# SFT_MotorController1_0v.net
KiCad netlist of a schematic drawn in EAGLE
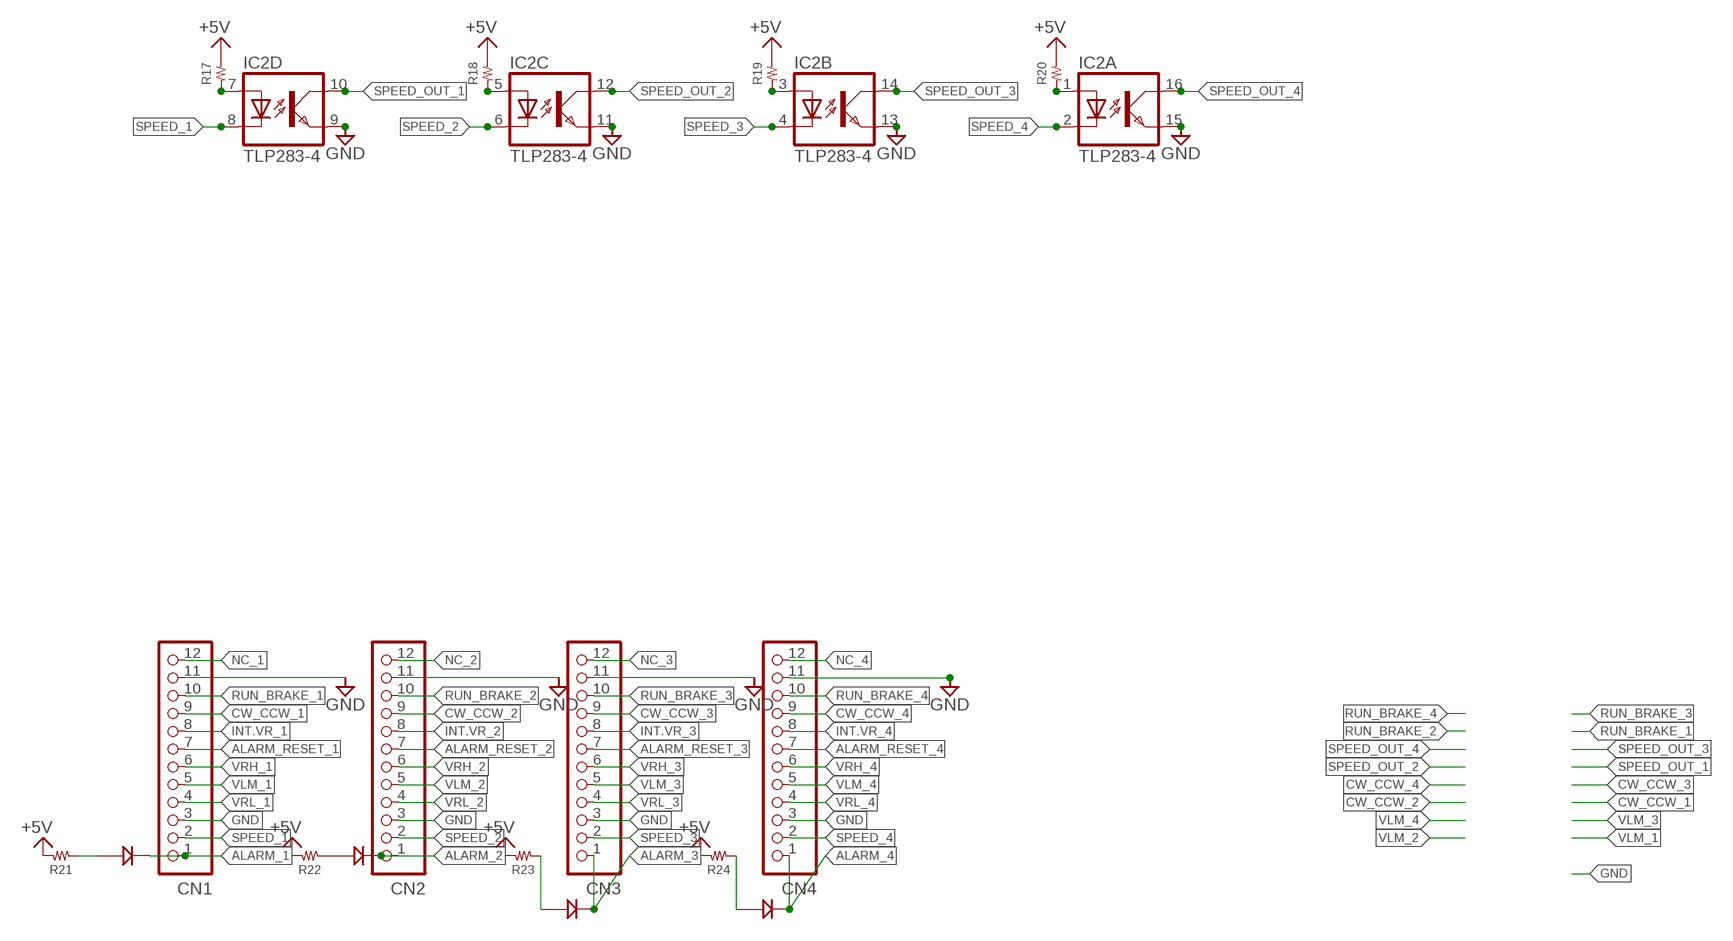
[diagram p0: schematic, sheet 1, part 1 of 2]
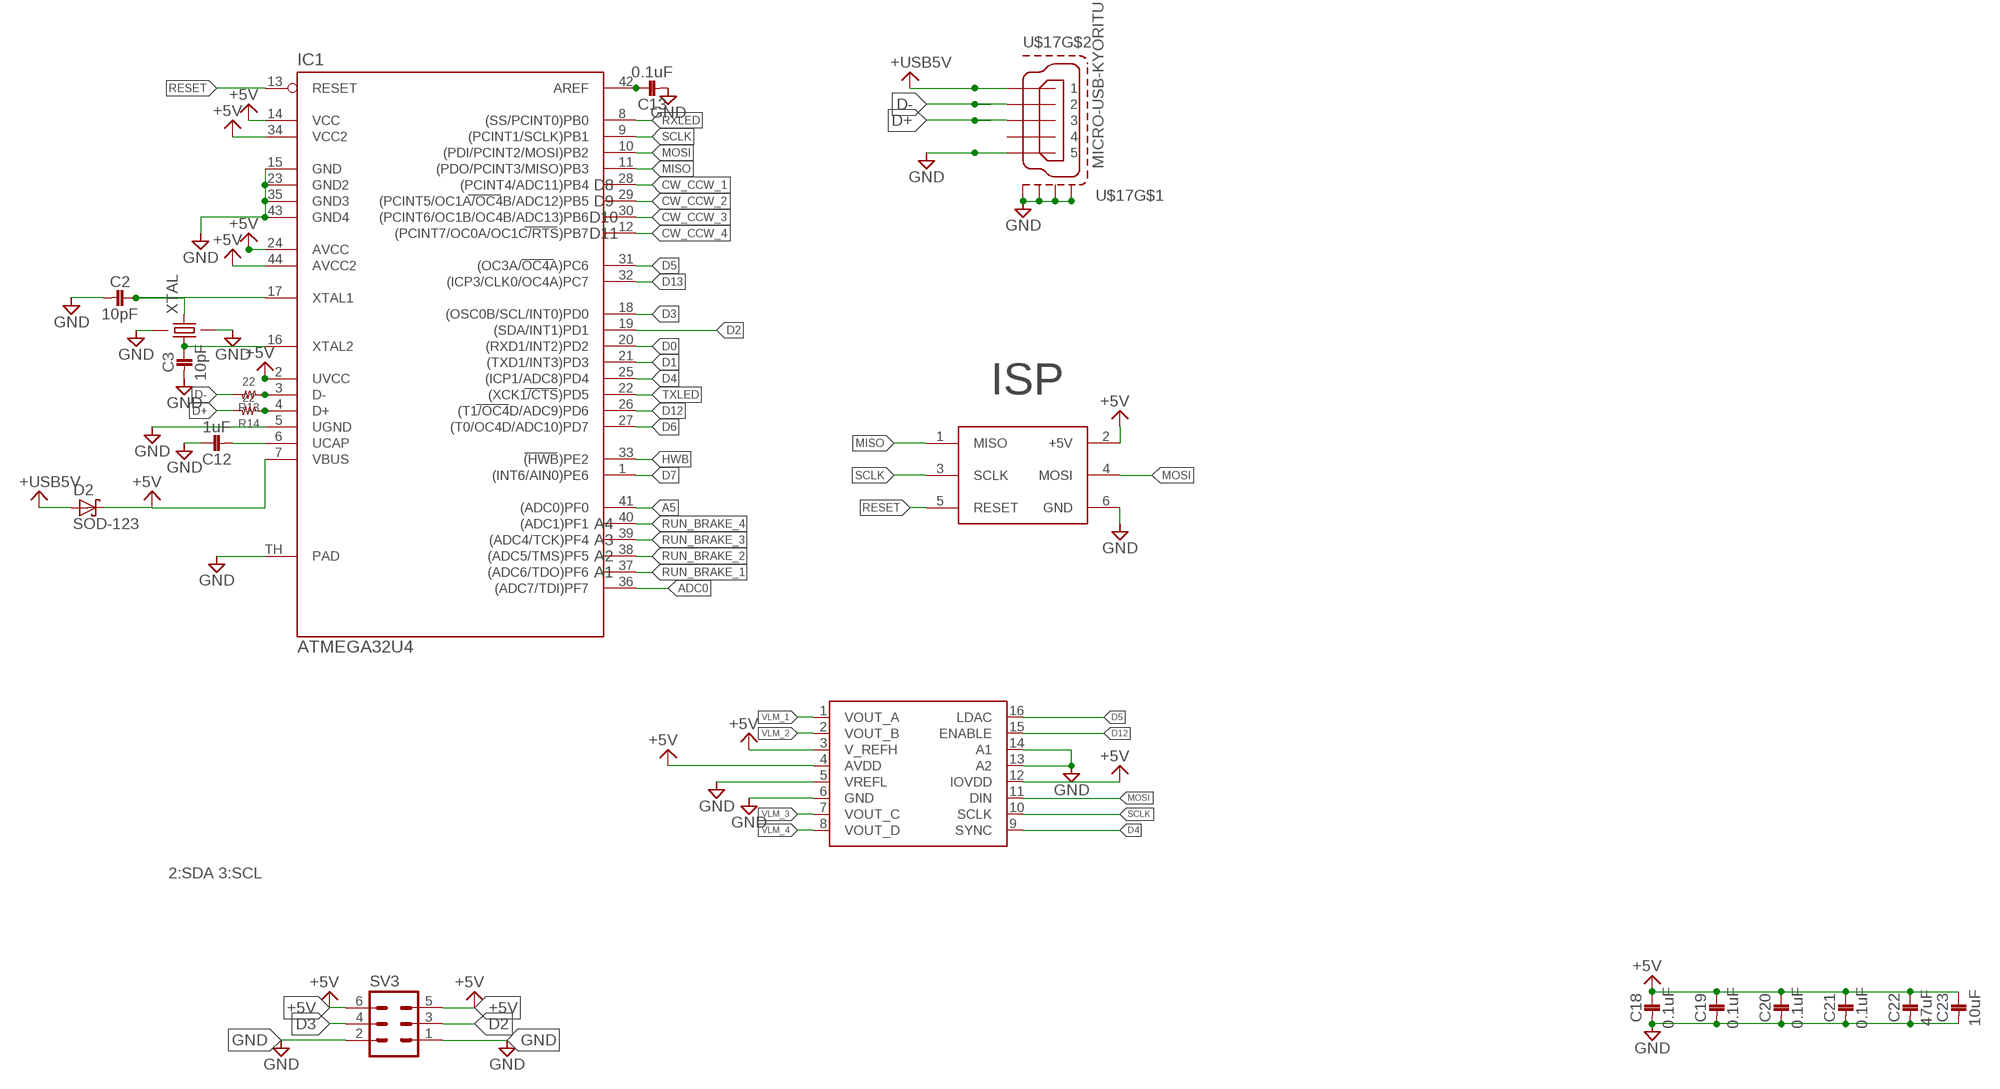
[diagram p1: schematic, sheet 1, part 2 of 2]

(export (version "E")
  (design (tool "Eeschema 10.0.6"))
  (components
    (comp (ref "C2")
      (value "10pF")
      (footprint "eagle-import:1005")
      (libsource (lib "eagle-import") (part "1005"))
    )
    (comp (ref "C3")
      (value "10pF")
      (footprint "eagle-import:1005")
      (libsource (lib "eagle-import") (part "1005"))
    )
    (comp (ref "C12")
      (value "1uF")
      (footprint "eagle-import:1005")
      (libsource (lib "eagle-import") (part "1005"))
    )
    (comp (ref "C13")
      (value "0.1uF")
      (footprint "eagle-import:1005")
      (libsource (lib "eagle-import") (part "1005"))
    )
    (comp (ref "C18")
      (value "0.1uF")
      (footprint "eagle-import:1005")
      (libsource (lib "eagle-import") (part "1005"))
    )
    (comp (ref "C19")
      (value "0.1uF")
      (footprint "eagle-import:1005")
      (libsource (lib "eagle-import") (part "1005"))
    )
    (comp (ref "C20")
      (value "0.1uF")
      (footprint "eagle-import:1005")
      (libsource (lib "eagle-import") (part "1005"))
    )
    (comp (ref "C21")
      (value "0.1uF")
      (footprint "eagle-import:1005")
      (libsource (lib "eagle-import") (part "1005"))
    )
    (comp (ref "C22")
      (value "47uF")
      (footprint "eagle-import:1608")
      (libsource (lib "eagle-import") (part "1608"))
    )
    (comp (ref "C23")
      (value "10uF")
      (footprint "eagle-import:1608")
      (libsource (lib "eagle-import") (part "1608"))
    )
    (comp (ref "CN1")
      (value "B12B-XASK-1")
      (footprint "eagle-import:B12B-XASK-1")
      (libsource (lib "eagle-import") (part "B12B-XASK-1"))
    )
    (comp (ref "CN2")
      (value "B12B-XASK-1")
      (footprint "eagle-import:B12B-XASK-1")
      (libsource (lib "eagle-import") (part "B12B-XASK-1"))
    )
    (comp (ref "CN3")
      (value "B12B-XASK-1")
      (footprint "eagle-import:B12B-XASK-1")
      (libsource (lib "eagle-import") (part "B12B-XASK-1"))
    )
    (comp (ref "CN4")
      (value "B12B-XASK-1")
      (footprint "eagle-import:B12B-XASK-1")
      (libsource (lib "eagle-import") (part "B12B-XASK-1"))
    )
    (comp (ref "D2")
      (value "SOD-123")
      (footprint "eagle-import:SOD_123")
      (libsource (lib "eagle-import") (part "SOD-123"))
    )
    (comp (ref "IC1")
      (value "ATMEGA32U4")
      (footprint "eagle-import:QFN-44-7X7")
      (libsource (lib "eagle-import") (part "ATMEGA32U4"))
    )
    (comp (ref "IC2")
      (value "TLP283-4")
      (footprint "eagle-import:MINI-FLAT-16")
      (libsource (lib "eagle-import") (part "TLP283-4"))
    )
    (comp (ref "IC3")
      (value "DAC7564")
      (footprint "eagle-import:TSSOP16")
      (libsource (lib "eagle-import") (part "DAC7564"))
    )
    (comp (ref "R13")
      (value "22")
      (footprint "eagle-import:1005")
      (libsource (lib "eagle-import") (part "RESISTOR_1005"))
    )
    (comp (ref "R14")
      (value "22")
      (footprint "eagle-import:1005")
      (libsource (lib "eagle-import") (part "RESISTOR_1005"))
    )
    (comp (ref "R17")
      (value "RESISTOR__SMD")
      (footprint "eagle-import:1608")
      (libsource (lib "eagle-import") (part "RESISTOR__SMD"))
    )
    (comp (ref "R18")
      (value "RESISTOR__SMD")
      (footprint "eagle-import:1608")
      (libsource (lib "eagle-import") (part "RESISTOR__SMD"))
    )
    (comp (ref "R19")
      (value "RESISTOR__SMD")
      (footprint "eagle-import:1608")
      (libsource (lib "eagle-import") (part "RESISTOR__SMD"))
    )
    (comp (ref "R20")
      (value "RESISTOR__SMD")
      (footprint "eagle-import:1608")
      (libsource (lib "eagle-import") (part "RESISTOR__SMD"))
    )
    (comp (ref "R21")
      (value "RESISTOR__SMD")
      (footprint "eagle-import:1608")
      (libsource (lib "eagle-import") (part "RESISTOR__SMD"))
    )
    (comp (ref "R22")
      (value "RESISTOR__SMD")
      (footprint "eagle-import:1608")
      (libsource (lib "eagle-import") (part "RESISTOR__SMD"))
    )
    (comp (ref "R23")
      (value "RESISTOR__SMD")
      (footprint "eagle-import:1608")
      (libsource (lib "eagle-import") (part "RESISTOR__SMD"))
    )
    (comp (ref "R24")
      (value "RESISTOR__SMD")
      (footprint "eagle-import:1608")
      (libsource (lib "eagle-import") (part "RESISTOR__SMD"))
    )
    (comp (ref "SV3")
      (value "ML6")
      (footprint "eagle-import:ML6")
      (libsource (lib "eagle-import") (part "ML6"))
    )
    (comp (ref "U$8")
      (value "ICSP")
      (footprint "eagle-import:ICSP")
      (libsource (lib "eagle-import") (part "ICSP"))
    )
    (comp (ref "U$17")
      (value "MICRO-USB-KYORITU")
      (footprint "eagle-import:ZX62R-B-5P")
      (libsource (lib "eagle-import") (part "MICRO-USB-KYORITU"))
    )
    (comp (ref "U$36")
      (value "3MMLED")
      (footprint "eagle-import:3MM")
      (libsource (lib "eagle-import") (part "3MMLED"))
    )
    (comp (ref "U$37")
      (value "3MMLED")
      (footprint "eagle-import:3MM")
      (libsource (lib "eagle-import") (part "3MMLED"))
    )
    (comp (ref "U$38")
      (value "3MMLED")
      (footprint "eagle-import:3MM")
      (libsource (lib "eagle-import") (part "3MMLED"))
    )
    (comp (ref "U$39")
      (value "3MMLED")
      (footprint "eagle-import:3MM")
      (libsource (lib "eagle-import") (part "3MMLED"))
    )
    (comp (ref "XTAL")
      (value "FA-238")
      (footprint "eagle-import:FA-238")
      (libsource (lib "eagle-import") (part "FA-238"))
    )
  )
  (nets
    (net (code "1") (name "+5V") (class "Default")
      (node (ref "C18") (pin "1") (pinfunction "1_1") (pintype "passive"))
      (node (ref "C19") (pin "1") (pinfunction "1_1") (pintype "passive"))
      (node (ref "C20") (pin "1") (pinfunction "1_1") (pintype "passive"))
      (node (ref "C21") (pin "1") (pinfunction "1_1") (pintype "passive"))
      (node (ref "C22") (pin "P$1") (pinfunction "1_P$1") (pintype "passive"))
      (node (ref "C23") (pin "P$1") (pinfunction "1_P$1") (pintype "passive"))
      (node (ref "D2") (pin "C") (pinfunction "C_C") (pintype "passive"))
      (node (ref "IC1") (pin "14") (pinfunction "VCC_14") (pintype "bidirectional"))
      (node (ref "IC1") (pin "2") (pinfunction "UVCC_2") (pintype "bidirectional"))
      (node (ref "IC1") (pin "24") (pinfunction "AVCC_24") (pintype "bidirectional"))
      (node (ref "IC1") (pin "34") (pinfunction "VCC2_34") (pintype "bidirectional"))
      (node (ref "IC1") (pin "44") (pinfunction "AVCC2_44") (pintype "bidirectional"))
      (node (ref "IC1") (pin "7") (pinfunction "VBUS_7") (pintype "bidirectional"))
      (node (ref "IC3") (pin "12") (pinfunction "IOVDD_12") (pintype "bidirectional"))
      (node (ref "IC3") (pin "3") (pinfunction "V_REFH_3") (pintype "bidirectional"))
      (node (ref "IC3") (pin "4") (pinfunction "AVDD_4") (pintype "bidirectional"))
      (node (ref "R17") (pin "2") (pinfunction "P$2_2") (pintype "passive"))
      (node (ref "R18") (pin "2") (pinfunction "P$2_2") (pintype "passive"))
      (node (ref "R19") (pin "2") (pinfunction "P$2_2") (pintype "passive"))
      (node (ref "R20") (pin "2") (pinfunction "P$2_2") (pintype "passive"))
      (node (ref "R21") (pin "2") (pinfunction "P$2_2") (pintype "passive"))
      (node (ref "R22") (pin "2") (pinfunction "P$2_2") (pintype "passive"))
      (node (ref "R23") (pin "2") (pinfunction "P$2_2") (pintype "passive"))
      (node (ref "R24") (pin "2") (pinfunction "P$2_2") (pintype "passive"))
      (node (ref "SV3") (pin "5") (pinfunction "5_5") (pintype "passive"))
      (node (ref "SV3") (pin "6") (pinfunction "6_6") (pintype "passive"))
      (node (ref "U$8") (pin "2") (pinfunction "+5V_2") (pintype "bidirectional"))
    )
    (net (code "2") (name "+USB5V") (class "Default")
      (node (ref "D2") (pin "A") (pinfunction "A_A") (pintype "passive"))
      (node (ref "U$17") (pin "5") (pinfunction "1_5") (pintype "input"))
    )
    (net (code "3") (name "A5") (class "Default")
      (node (ref "IC1") (pin "41") (pinfunction "(ADC0)PF0_41") (pintype "bidirectional"))
    )
    (net (code "4") (name "ADC0") (class "Default")
      (node (ref "IC1") (pin "36") (pinfunction "(ADC7/TDI)PF7_36") (pintype "bidirectional"))
    )
    (net (code "5") (name "ALARM_1") (class "Default")
      (node (ref "CN1") (pin "1") (pinfunction "1_1") (pintype "passive"))
      (node (ref "U$37") (pin "K") (pinfunction "K_K") (pintype "bidirectional"))
    )
    (net (code "6") (name "ALARM_2") (class "Default")
      (node (ref "CN2") (pin "1") (pinfunction "1_1") (pintype "passive"))
      (node (ref "U$38") (pin "K") (pinfunction "K_K") (pintype "bidirectional"))
    )
    (net (code "7") (name "ALARM_3") (class "Default")
      (node (ref "CN3") (pin "1") (pinfunction "1_1") (pintype "passive"))
      (node (ref "U$36") (pin "K") (pinfunction "K_K") (pintype "bidirectional"))
    )
    (net (code "8") (name "ALARM_4") (class "Default")
      (node (ref "CN4") (pin "1") (pinfunction "1_1") (pintype "passive"))
      (node (ref "U$39") (pin "K") (pinfunction "K_K") (pintype "bidirectional"))
    )
    (net (code "9") (name "ALARM_RESET_1") (class "Default")
      (node (ref "CN1") (pin "7") (pinfunction "7_7") (pintype "passive"))
    )
    (net (code "10") (name "ALARM_RESET_2") (class "Default")
      (node (ref "CN2") (pin "7") (pinfunction "7_7") (pintype "passive"))
    )
    (net (code "11") (name "ALARM_RESET_3") (class "Default")
      (node (ref "CN3") (pin "7") (pinfunction "7_7") (pintype "passive"))
    )
    (net (code "12") (name "ALARM_RESET_4") (class "Default")
      (node (ref "CN4") (pin "7") (pinfunction "7_7") (pintype "passive"))
    )
    (net (code "13") (name "CW_CCW_1") (class "Default")
      (node (ref "CN1") (pin "9") (pinfunction "9_9") (pintype "passive"))
      (node (ref "IC1") (pin "28") (pinfunction "(PCINT4/ADC11)PB4_28") (pintype "bidirectional"))
    )
    (net (code "14") (name "CW_CCW_2") (class "Default")
      (node (ref "CN2") (pin "9") (pinfunction "9_9") (pintype "passive"))
      (node (ref "IC1") (pin "29") (pinfunction "(PCINT5/OC1A/OC4B/ADC12)PB5_29") (pintype "bidirectional"))
    )
    (net (code "15") (name "CW_CCW_3") (class "Default")
      (node (ref "CN3") (pin "9") (pinfunction "9_9") (pintype "passive"))
      (node (ref "IC1") (pin "30") (pinfunction "(PCINT6/OC1B/OC4B/ADC13)PB6_30") (pintype "bidirectional"))
    )
    (net (code "16") (name "CW_CCW_4") (class "Default")
      (node (ref "CN4") (pin "9") (pinfunction "9_9") (pintype "passive"))
      (node (ref "IC1") (pin "12") (pinfunction "(PCINT7/OC0A/OC1C/RTS)PB7_12") (pintype "bidirectional"))
    )
    (net (code "17") (name "D+") (class "Default")
      (node (ref "R14") (pin "2") (pinfunction "P$2_2") (pintype "passive"))
      (node (ref "U$17") (pin "3") (pinfunction "3_3") (pintype "input"))
    )
    (net (code "18") (name "D-") (class "Default")
      (node (ref "R13") (pin "2") (pinfunction "P$2_2") (pintype "passive"))
      (node (ref "U$17") (pin "4") (pinfunction "2_4") (pintype "input"))
    )
    (net (code "19") (name "D0") (class "Default")
      (node (ref "IC1") (pin "20") (pinfunction "(RXD1/INT2)PD2_20") (pintype "bidirectional"))
    )
    (net (code "20") (name "D1") (class "Default")
      (node (ref "IC1") (pin "21") (pinfunction "(TXD1/INT3)PD3_21") (pintype "bidirectional"))
    )
    (net (code "21") (name "D2") (class "Default")
      (node (ref "IC1") (pin "19") (pinfunction "(SDA/INT1)PD1_19") (pintype "bidirectional"))
      (node (ref "SV3") (pin "3") (pinfunction "3_3") (pintype "passive"))
    )
    (net (code "22") (name "D3") (class "Default")
      (node (ref "IC1") (pin "18") (pinfunction "(OSC0B/SCL/INT0)PD0_18") (pintype "bidirectional"))
      (node (ref "SV3") (pin "4") (pinfunction "4_4") (pintype "passive"))
    )
    (net (code "23") (name "D4") (class "Default")
      (node (ref "IC1") (pin "25") (pinfunction "(ICP1/ADC8)PD4_25") (pintype "bidirectional"))
      (node (ref "IC3") (pin "9") (pinfunction "SYNC_9") (pintype "bidirectional"))
    )
    (net (code "24") (name "D5") (class "Default")
      (node (ref "IC1") (pin "31") (pinfunction "(OC3A/OC4A)PC6_31") (pintype "bidirectional"))
      (node (ref "IC3") (pin "16") (pinfunction "LDAC_16") (pintype "bidirectional"))
    )
    (net (code "25") (name "D6") (class "Default")
      (node (ref "IC1") (pin "27") (pinfunction "(T0/OC4D/ADC10)PD7_27") (pintype "bidirectional"))
    )
    (net (code "26") (name "D7") (class "Default")
      (node (ref "IC1") (pin "1") (pinfunction "(INT6/AIN0)PE6_1") (pintype "bidirectional"))
    )
    (net (code "27") (name "D12") (class "Default")
      (node (ref "IC1") (pin "26") (pinfunction "(T1/OC4D/ADC9)PD6_26") (pintype "bidirectional"))
      (node (ref "IC3") (pin "15") (pinfunction "ENABLE_15") (pintype "bidirectional"))
    )
    (net (code "28") (name "D13") (class "Default")
      (node (ref "IC1") (pin "32") (pinfunction "(ICP3/CLK0/OC4A)PC7_32") (pintype "bidirectional"))
    )
    (net (code "29") (name "GND") (class "Default")
      (node (ref "C12") (pin "1") (pinfunction "1_1") (pintype "passive"))
      (node (ref "C13") (pin "2") (pinfunction "2_2") (pintype "passive"))
      (node (ref "C18") (pin "2") (pinfunction "2_2") (pintype "passive"))
      (node (ref "C19") (pin "2") (pinfunction "2_2") (pintype "passive"))
      (node (ref "C2") (pin "2") (pinfunction "2_2") (pintype "passive"))
      (node (ref "C20") (pin "2") (pinfunction "2_2") (pintype "passive"))
      (node (ref "C21") (pin "2") (pinfunction "2_2") (pintype "passive"))
      (node (ref "C22") (pin "P$2") (pinfunction "2_P$2") (pintype "passive"))
      (node (ref "C23") (pin "P$2") (pinfunction "2_P$2") (pintype "passive"))
      (node (ref "C3") (pin "2") (pinfunction "2_2") (pintype "passive"))
      (node (ref "CN1") (pin "11") (pinfunction "11_11") (pintype "passive"))
      (node (ref "CN1") (pin "3") (pinfunction "3_3") (pintype "passive"))
      (node (ref "CN2") (pin "11") (pinfunction "11_11") (pintype "passive"))
      (node (ref "CN2") (pin "3") (pinfunction "3_3") (pintype "passive"))
      (node (ref "CN3") (pin "11") (pinfunction "11_11") (pintype "passive"))
      (node (ref "CN3") (pin "3") (pinfunction "3_3") (pintype "passive"))
      (node (ref "CN4") (pin "11") (pinfunction "11_11") (pintype "passive"))
      (node (ref "CN4") (pin "3") (pinfunction "3_3") (pintype "passive"))
      (node (ref "IC1") (pin "15") (pinfunction "GND_15") (pintype "bidirectional"))
      (node (ref "IC1") (pin "23") (pinfunction "GND2_23") (pintype "bidirectional"))
      (node (ref "IC1") (pin "35") (pinfunction "GND3_35") (pintype "bidirectional"))
      (node (ref "IC1") (pin "43") (pinfunction "GND4_43") (pintype "bidirectional"))
      (node (ref "IC1") (pin "5") (pinfunction "UGND_5") (pintype "bidirectional"))
      (node (ref "IC1") (pin "TH") (pinfunction "PAD_TH") (pintype "bidirectional"))
      (node (ref "IC2") (pin "11") (pinfunction "EMIT_11") (pintype "passive"))
      (node (ref "IC2") (pin "13") (pinfunction "EMIT_13") (pintype "passive"))
      (node (ref "IC2") (pin "15") (pinfunction "EMIT_15") (pintype "passive"))
      (node (ref "IC2") (pin "9") (pinfunction "EMIT_9") (pintype "passive"))
      (node (ref "IC3") (pin "13") (pinfunction "A2_13") (pintype "bidirectional"))
      (node (ref "IC3") (pin "14") (pinfunction "A1_14") (pintype "bidirectional"))
      (node (ref "IC3") (pin "5") (pinfunction "VREFL_5") (pintype "bidirectional"))
      (node (ref "IC3") (pin "6") (pinfunction "GND_6") (pintype "bidirectional"))
      (node (ref "SV3") (pin "1") (pinfunction "1_1") (pintype "passive"))
      (node (ref "SV3") (pin "2") (pinfunction "2_2") (pintype "passive"))
      (node (ref "U$17") (pin "1") (pinfunction "5_1") (pintype "input"))
      (node (ref "U$17") (pin "M1") (pinfunction "S1_M1") (pintype "passive"))
      (node (ref "U$17") (pin "M2") (pinfunction "S2_M2") (pintype "passive"))
      (node (ref "U$17") (pin "M3") (pinfunction "S3_M3") (pintype "passive"))
      (node (ref "U$17") (pin "M4") (pinfunction "S4_M4") (pintype "passive"))
      (node (ref "U$8") (pin "6") (pinfunction "GND_6") (pintype "bidirectional"))
      (node (ref "XTAL") (pin "2") (pinfunction "2_2") (pintype "bidirectional"))
      (node (ref "XTAL") (pin "4") (pinfunction "4_4") (pintype "bidirectional"))
    )
    (net (code "30") (name "HWB") (class "Default")
      (node (ref "IC1") (pin "33") (pinfunction "(HWB)PE2_33") (pintype "bidirectional"))
    )
    (net (code "31") (name "INT.VR_1") (class "Default")
      (node (ref "CN1") (pin "8") (pinfunction "8_8") (pintype "passive"))
    )
    (net (code "32") (name "INT.VR_2") (class "Default")
      (node (ref "CN2") (pin "8") (pinfunction "8_8") (pintype "passive"))
    )
    (net (code "33") (name "INT.VR_3") (class "Default")
      (node (ref "CN3") (pin "8") (pinfunction "8_8") (pintype "passive"))
    )
    (net (code "34") (name "INT.VR_4") (class "Default")
      (node (ref "CN4") (pin "8") (pinfunction "8_8") (pintype "passive"))
    )
    (net (code "35") (name "MISO") (class "Default")
      (node (ref "IC1") (pin "11") (pinfunction "(PDO/PCINT3/MISO)PB3_11") (pintype "bidirectional"))
      (node (ref "U$8") (pin "1") (pinfunction "MISO_1") (pintype "bidirectional"))
    )
    (net (code "36") (name "MOSI") (class "Default")
      (node (ref "IC1") (pin "10") (pinfunction "(PDI/PCINT2/MOSI)PB2_10") (pintype "bidirectional"))
      (node (ref "IC3") (pin "11") (pinfunction "DIN_11") (pintype "bidirectional"))
      (node (ref "U$8") (pin "4") (pinfunction "MOSI_4") (pintype "bidirectional"))
    )
    (net (code "37") (name "NC_1") (class "Default")
      (node (ref "CN1") (pin "12") (pinfunction "12_12") (pintype "passive"))
    )
    (net (code "38") (name "NC_2") (class "Default")
      (node (ref "CN2") (pin "12") (pinfunction "12_12") (pintype "passive"))
    )
    (net (code "39") (name "NC_3") (class "Default")
      (node (ref "CN3") (pin "12") (pinfunction "12_12") (pintype "passive"))
    )
    (net (code "40") (name "NC_4") (class "Default")
      (node (ref "CN4") (pin "12") (pinfunction "12_12") (pintype "passive"))
    )
    (net (code "41") (name "Net-(IC1-AREF)") (class "Default")
      (node (ref "C13") (pin "1") (pinfunction "1_1") (pintype "passive"))
      (node (ref "IC1") (pin "42") (pinfunction "AREF_42") (pintype "bidirectional"))
    )
    (net (code "42") (name "Net-(IC1-D+)") (class "Default")
      (node (ref "IC1") (pin "4") (pinfunction "D+_4") (pintype "bidirectional"))
      (node (ref "R14") (pin "1") (pinfunction "P$1_1") (pintype "passive"))
    )
    (net (code "43") (name "Net-(IC1-D-)") (class "Default")
      (node (ref "IC1") (pin "3") (pinfunction "D-_3") (pintype "bidirectional"))
      (node (ref "R13") (pin "1") (pinfunction "P$1_1") (pintype "passive"))
    )
    (net (code "44") (name "Net-(IC1-UCAP)") (class "Default")
      (node (ref "C12") (pin "2") (pinfunction "2_2") (pintype "passive"))
      (node (ref "IC1") (pin "6") (pinfunction "UCAP_6") (pintype "bidirectional"))
    )
    (net (code "45") (name "Net-(IC1-XTAL1)") (class "Default")
      (node (ref "C2") (pin "1") (pinfunction "1_1") (pintype "passive"))
      (node (ref "IC1") (pin "17") (pinfunction "XTAL1_17") (pintype "bidirectional"))
      (node (ref "XTAL") (pin "3") (pinfunction "3_3") (pintype "passive"))
    )
    (net (code "46") (name "Net-(IC1-XTAL2)") (class "Default")
      (node (ref "C3") (pin "1") (pinfunction "1_1") (pintype "passive"))
      (node (ref "IC1") (pin "16") (pinfunction "XTAL2_16") (pintype "bidirectional"))
      (node (ref "XTAL") (pin "1") (pinfunction "1_1") (pintype "passive"))
    )
    (net (code "47") (name "Net-(IC2A-A)") (class "Default")
      (node (ref "IC2") (pin "1") (pinfunction "A_1") (pintype "passive"))
      (node (ref "R20") (pin "1") (pinfunction "P$1_1") (pintype "passive"))
    )
    (net (code "48") (name "Net-(IC2B-A)") (class "Default")
      (node (ref "IC2") (pin "3") (pinfunction "A_3") (pintype "passive"))
      (node (ref "R19") (pin "1") (pinfunction "P$1_1") (pintype "passive"))
    )
    (net (code "49") (name "Net-(IC2C-A)") (class "Default")
      (node (ref "IC2") (pin "5") (pinfunction "A_5") (pintype "passive"))
      (node (ref "R18") (pin "1") (pinfunction "P$1_1") (pintype "passive"))
    )
    (net (code "50") (name "Net-(IC2D-A)") (class "Default")
      (node (ref "IC2") (pin "7") (pinfunction "A_7") (pintype "passive"))
      (node (ref "R17") (pin "1") (pinfunction "P$1_1") (pintype "passive"))
    )
    (net (code "51") (name "Net-(R21-P$1)") (class "Default")
      (node (ref "R21") (pin "1") (pinfunction "P$1_1") (pintype "passive"))
      (node (ref "U$37") (pin "A") (pinfunction "A_A") (pintype "bidirectional"))
    )
    (net (code "52") (name "Net-(R22-P$1)") (class "Default")
      (node (ref "R22") (pin "1") (pinfunction "P$1_1") (pintype "passive"))
      (node (ref "U$38") (pin "A") (pinfunction "A_A") (pintype "bidirectional"))
    )
    (net (code "53") (name "Net-(R23-P$1)") (class "Default")
      (node (ref "R23") (pin "1") (pinfunction "P$1_1") (pintype "passive"))
      (node (ref "U$36") (pin "A") (pinfunction "A_A") (pintype "bidirectional"))
    )
    (net (code "54") (name "Net-(R24-P$1)") (class "Default")
      (node (ref "R24") (pin "1") (pinfunction "P$1_1") (pintype "passive"))
      (node (ref "U$39") (pin "A") (pinfunction "A_A") (pintype "bidirectional"))
    )
    (net (code "55") (name "RESET") (class "Default")
      (node (ref "IC1") (pin "13") (pinfunction "RESET_13") (pintype "bidirectional"))
      (node (ref "U$8") (pin "5") (pinfunction "RESET_5") (pintype "bidirectional"))
    )
    (net (code "56") (name "RUN_BRAKE_1") (class "Default")
      (node (ref "CN1") (pin "10") (pinfunction "10_10") (pintype "passive"))
      (node (ref "IC1") (pin "37") (pinfunction "(ADC6/TDO)PF6_37") (pintype "bidirectional"))
    )
    (net (code "57") (name "RUN_BRAKE_2") (class "Default")
      (node (ref "CN2") (pin "10") (pinfunction "10_10") (pintype "passive"))
      (node (ref "IC1") (pin "38") (pinfunction "(ADC5/TMS)PF5_38") (pintype "bidirectional"))
    )
    (net (code "58") (name "RUN_BRAKE_3") (class "Default")
      (node (ref "CN3") (pin "10") (pinfunction "10_10") (pintype "passive"))
      (node (ref "IC1") (pin "39") (pinfunction "(ADC4/TCK)PF4_39") (pintype "bidirectional"))
    )
    (net (code "59") (name "RUN_BRAKE_4") (class "Default")
      (node (ref "CN4") (pin "10") (pinfunction "10_10") (pintype "passive"))
      (node (ref "IC1") (pin "40") (pinfunction "(ADC1)PF1_40") (pintype "bidirectional"))
    )
    (net (code "60") (name "RXLED") (class "Default")
      (node (ref "IC1") (pin "8") (pinfunction "(SS/PCINT0)PB0_8") (pintype "bidirectional"))
    )
    (net (code "61") (name "SCLK") (class "Default")
      (node (ref "IC1") (pin "9") (pinfunction "(PCINT1/SCLK)PB1_9") (pintype "bidirectional"))
      (node (ref "IC3") (pin "10") (pinfunction "SCLK_10") (pintype "bidirectional"))
      (node (ref "U$8") (pin "3") (pinfunction "SCLK_3") (pintype "bidirectional"))
    )
    (net (code "62") (name "SPEED_1") (class "Default")
      (node (ref "CN1") (pin "2") (pinfunction "2_2") (pintype "passive"))
      (node (ref "IC2") (pin "8") (pinfunction "C_8") (pintype "passive"))
    )
    (net (code "63") (name "SPEED_2") (class "Default")
      (node (ref "CN2") (pin "2") (pinfunction "2_2") (pintype "passive"))
      (node (ref "IC2") (pin "6") (pinfunction "C_6") (pintype "passive"))
    )
    (net (code "64") (name "SPEED_3") (class "Default")
      (node (ref "CN3") (pin "2") (pinfunction "2_2") (pintype "passive"))
      (node (ref "IC2") (pin "4") (pinfunction "C_4") (pintype "passive"))
    )
    (net (code "65") (name "SPEED_4") (class "Default")
      (node (ref "CN4") (pin "2") (pinfunction "2_2") (pintype "passive"))
      (node (ref "IC2") (pin "2") (pinfunction "C_2") (pintype "passive"))
    )
    (net (code "66") (name "SPEED_OUT_1") (class "Default")
      (node (ref "IC2") (pin "10") (pinfunction "COL_10") (pintype "passive"))
    )
    (net (code "67") (name "SPEED_OUT_2") (class "Default")
      (node (ref "IC2") (pin "12") (pinfunction "COL_12") (pintype "passive"))
    )
    (net (code "68") (name "SPEED_OUT_3") (class "Default")
      (node (ref "IC2") (pin "14") (pinfunction "COL_14") (pintype "passive"))
    )
    (net (code "69") (name "SPEED_OUT_4") (class "Default")
      (node (ref "IC2") (pin "16") (pinfunction "COL_16") (pintype "passive"))
    )
    (net (code "70") (name "TXLED") (class "Default")
      (node (ref "IC1") (pin "22") (pinfunction "(XCK1/CTS)PD5_22") (pintype "bidirectional"))
    )
    (net (code "71") (name "VLM_1") (class "Default")
      (node (ref "CN1") (pin "5") (pinfunction "5_5") (pintype "passive"))
      (node (ref "IC3") (pin "1") (pinfunction "VOUT_A_1") (pintype "bidirectional"))
    )
    (net (code "72") (name "VLM_2") (class "Default")
      (node (ref "CN2") (pin "5") (pinfunction "5_5") (pintype "passive"))
      (node (ref "IC3") (pin "2") (pinfunction "VOUT_B_2") (pintype "bidirectional"))
    )
    (net (code "73") (name "VLM_3") (class "Default")
      (node (ref "CN3") (pin "5") (pinfunction "5_5") (pintype "passive"))
      (node (ref "IC3") (pin "7") (pinfunction "VOUT_C_7") (pintype "bidirectional"))
    )
    (net (code "74") (name "VLM_4") (class "Default")
      (node (ref "CN4") (pin "5") (pinfunction "5_5") (pintype "passive"))
      (node (ref "IC3") (pin "8") (pinfunction "VOUT_D_8") (pintype "bidirectional"))
    )
    (net (code "75") (name "VRH_1") (class "Default")
      (node (ref "CN1") (pin "6") (pinfunction "6_6") (pintype "passive"))
    )
    (net (code "76") (name "VRH_2") (class "Default")
      (node (ref "CN2") (pin "6") (pinfunction "6_6") (pintype "passive"))
    )
    (net (code "77") (name "VRH_3") (class "Default")
      (node (ref "CN3") (pin "6") (pinfunction "6_6") (pintype "passive"))
    )
    (net (code "78") (name "VRH_4") (class "Default")
      (node (ref "CN4") (pin "6") (pinfunction "6_6") (pintype "passive"))
    )
    (net (code "79") (name "VRL_1") (class "Default")
      (node (ref "CN1") (pin "4") (pinfunction "4_4") (pintype "passive"))
    )
    (net (code "80") (name "VRL_2") (class "Default")
      (node (ref "CN2") (pin "4") (pinfunction "4_4") (pintype "passive"))
    )
    (net (code "81") (name "VRL_3") (class "Default")
      (node (ref "CN3") (pin "4") (pinfunction "4_4") (pintype "passive"))
    )
    (net (code "82") (name "VRL_4") (class "Default")
      (node (ref "CN4") (pin "4") (pinfunction "4_4") (pintype "passive"))
    )
    (net (code "83") (name "unconnected-(U$17B-4-Pad2)") (class "Default")
      (node (ref "U$17") (pin "2") (pinfunction "4_2") (pintype "input"))
    )
  )
)
